# 8iPanelDec.net
KiCad netlist of a schematic drawn in EAGLE
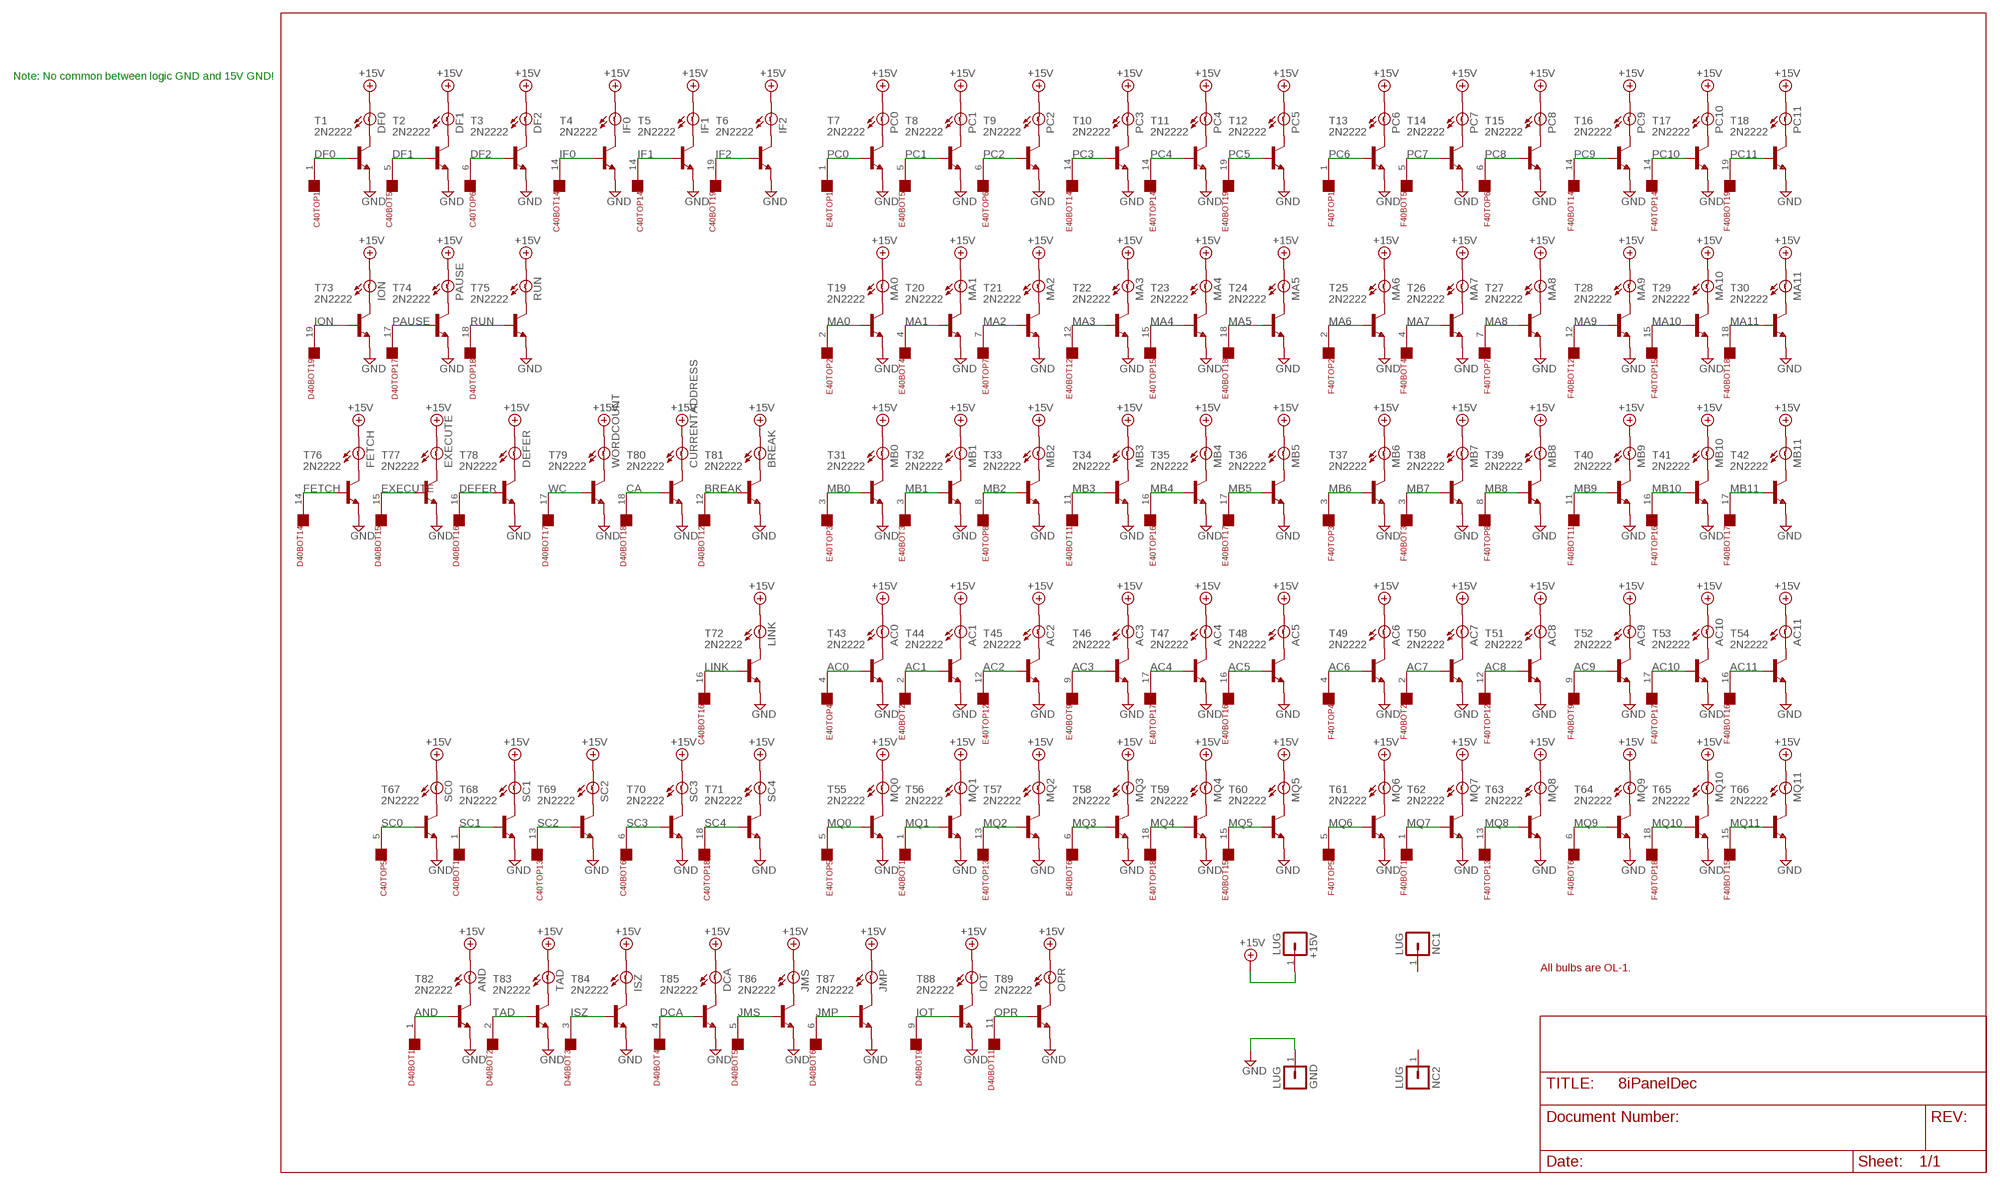
[diagram p0: schematic, sheet 1]

(export (version "E")
  (design (tool "Eeschema 10.0.6"))
  (components
    (comp (ref "+15V")
      (value "LUG")
      (footprint "eagle-import:SPADELUG")
      (libsource (lib "eagle-import") (part "LUG"))
    )
    (comp (ref "AC0")
      (value "BULB")
      (footprint "eagle-import:BULB")
      (libsource (lib "eagle-import") (part "BULB"))
    )
    (comp (ref "AC1")
      (value "BULB")
      (footprint "eagle-import:BULB")
      (libsource (lib "eagle-import") (part "BULB"))
    )
    (comp (ref "AC2")
      (value "BULB")
      (footprint "eagle-import:BULB")
      (libsource (lib "eagle-import") (part "BULB"))
    )
    (comp (ref "AC3")
      (value "BULB")
      (footprint "eagle-import:BULB")
      (libsource (lib "eagle-import") (part "BULB"))
    )
    (comp (ref "AC4")
      (value "BULB")
      (footprint "eagle-import:BULB")
      (libsource (lib "eagle-import") (part "BULB"))
    )
    (comp (ref "AC5")
      (value "BULB")
      (footprint "eagle-import:BULB")
      (libsource (lib "eagle-import") (part "BULB"))
    )
    (comp (ref "AC6")
      (value "BULB")
      (footprint "eagle-import:BULB")
      (libsource (lib "eagle-import") (part "BULB"))
    )
    (comp (ref "AC7")
      (value "BULB")
      (footprint "eagle-import:BULB")
      (libsource (lib "eagle-import") (part "BULB"))
    )
    (comp (ref "AC8")
      (value "BULB")
      (footprint "eagle-import:BULB")
      (libsource (lib "eagle-import") (part "BULB"))
    )
    (comp (ref "AC9")
      (value "BULB")
      (footprint "eagle-import:BULB")
      (libsource (lib "eagle-import") (part "BULB"))
    )
    (comp (ref "AC10")
      (value "BULB")
      (footprint "eagle-import:BULB")
      (libsource (lib "eagle-import") (part "BULB"))
    )
    (comp (ref "AC11")
      (value "BULB")
      (footprint "eagle-import:BULB")
      (libsource (lib "eagle-import") (part "BULB"))
    )
    (comp (ref "AND")
      (value "BULB")
      (footprint "eagle-import:BULB")
      (libsource (lib "eagle-import") (part "BULB"))
    )
    (comp (ref "BREAK")
      (value "BULB")
      (footprint "eagle-import:BULB")
      (libsource (lib "eagle-import") (part "BULB"))
    )
    (comp (ref "C40BOT")
      (value "FLEX19")
      (footprint "eagle-import:FLEX19")
      (libsource (lib "eagle-import") (part "FLEX19"))
    )
    (comp (ref "C40TOP")
      (value "FLEX19")
      (footprint "eagle-import:FLEX19")
      (libsource (lib "eagle-import") (part "FLEX19"))
    )
    (comp (ref "CURRENTADDRESS")
      (value "BULB")
      (footprint "eagle-import:BULB")
      (libsource (lib "eagle-import") (part "BULB"))
    )
    (comp (ref "D40BOT")
      (value "FLEX19")
      (footprint "eagle-import:FLEX19")
      (libsource (lib "eagle-import") (part "FLEX19"))
    )
    (comp (ref "D40TOP")
      (value "FLEX19")
      (footprint "eagle-import:FLEX19")
      (libsource (lib "eagle-import") (part "FLEX19"))
    )
    (comp (ref "DCA")
      (value "BULB")
      (footprint "eagle-import:BULB")
      (libsource (lib "eagle-import") (part "BULB"))
    )
    (comp (ref "DEFER")
      (value "BULB")
      (footprint "eagle-import:BULB")
      (libsource (lib "eagle-import") (part "BULB"))
    )
    (comp (ref "DF0")
      (value "BULB")
      (footprint "eagle-import:BULB")
      (libsource (lib "eagle-import") (part "BULB"))
    )
    (comp (ref "DF1")
      (value "BULB")
      (footprint "eagle-import:BULB")
      (libsource (lib "eagle-import") (part "BULB"))
    )
    (comp (ref "DF2")
      (value "BULB")
      (footprint "eagle-import:BULB")
      (libsource (lib "eagle-import") (part "BULB"))
    )
    (comp (ref "E40BOT")
      (value "FLEX19")
      (footprint "eagle-import:FLEX19")
      (libsource (lib "eagle-import") (part "FLEX19"))
    )
    (comp (ref "E40TOP")
      (value "FLEX19")
      (footprint "eagle-import:FLEX19")
      (libsource (lib "eagle-import") (part "FLEX19"))
    )
    (comp (ref "EXECUTE")
      (value "BULB")
      (footprint "eagle-import:BULB")
      (libsource (lib "eagle-import") (part "BULB"))
    )
    (comp (ref "F40BOT")
      (value "FLEX19")
      (footprint "eagle-import:FLEX19")
      (libsource (lib "eagle-import") (part "FLEX19"))
    )
    (comp (ref "F40TOP")
      (value "FLEX19")
      (footprint "eagle-import:FLEX19")
      (libsource (lib "eagle-import") (part "FLEX19"))
    )
    (comp (ref "FETCH")
      (value "BULB")
      (footprint "eagle-import:BULB")
      (libsource (lib "eagle-import") (part "BULB"))
    )
    (comp (ref "GND")
      (value "LUG")
      (footprint "eagle-import:SPADELUG")
      (libsource (lib "eagle-import") (part "LUG"))
    )
    (comp (ref "IF0")
      (value "BULB")
      (footprint "eagle-import:BULB")
      (libsource (lib "eagle-import") (part "BULB"))
    )
    (comp (ref "IF1")
      (value "BULB")
      (footprint "eagle-import:BULB")
      (libsource (lib "eagle-import") (part "BULB"))
    )
    (comp (ref "IF2")
      (value "BULB")
      (footprint "eagle-import:BULB")
      (libsource (lib "eagle-import") (part "BULB"))
    )
    (comp (ref "ION")
      (value "BULB")
      (footprint "eagle-import:BULB")
      (libsource (lib "eagle-import") (part "BULB"))
    )
    (comp (ref "IOT")
      (value "BULB")
      (footprint "eagle-import:BULB")
      (libsource (lib "eagle-import") (part "BULB"))
    )
    (comp (ref "ISZ")
      (value "BULB")
      (footprint "eagle-import:BULB")
      (libsource (lib "eagle-import") (part "BULB"))
    )
    (comp (ref "JMP")
      (value "BULB")
      (footprint "eagle-import:BULB")
      (libsource (lib "eagle-import") (part "BULB"))
    )
    (comp (ref "JMS")
      (value "BULB")
      (footprint "eagle-import:BULB")
      (libsource (lib "eagle-import") (part "BULB"))
    )
    (comp (ref "LINK")
      (value "BULB")
      (footprint "eagle-import:BULB")
      (libsource (lib "eagle-import") (part "BULB"))
    )
    (comp (ref "MA0")
      (value "BULB")
      (footprint "eagle-import:BULB")
      (libsource (lib "eagle-import") (part "BULB"))
    )
    (comp (ref "MA1")
      (value "BULB")
      (footprint "eagle-import:BULB")
      (libsource (lib "eagle-import") (part "BULB"))
    )
    (comp (ref "MA2")
      (value "BULB")
      (footprint "eagle-import:BULB")
      (libsource (lib "eagle-import") (part "BULB"))
    )
    (comp (ref "MA3")
      (value "BULB")
      (footprint "eagle-import:BULB")
      (libsource (lib "eagle-import") (part "BULB"))
    )
    (comp (ref "MA4")
      (value "BULB")
      (footprint "eagle-import:BULB")
      (libsource (lib "eagle-import") (part "BULB"))
    )
    (comp (ref "MA5")
      (value "BULB")
      (footprint "eagle-import:BULB")
      (libsource (lib "eagle-import") (part "BULB"))
    )
    (comp (ref "MA6")
      (value "BULB")
      (footprint "eagle-import:BULB")
      (libsource (lib "eagle-import") (part "BULB"))
    )
    (comp (ref "MA7")
      (value "BULB")
      (footprint "eagle-import:BULB")
      (libsource (lib "eagle-import") (part "BULB"))
    )
    (comp (ref "MA8")
      (value "BULB")
      (footprint "eagle-import:BULB")
      (libsource (lib "eagle-import") (part "BULB"))
    )
    (comp (ref "MA9")
      (value "BULB")
      (footprint "eagle-import:BULB")
      (libsource (lib "eagle-import") (part "BULB"))
    )
    (comp (ref "MA10")
      (value "BULB")
      (footprint "eagle-import:BULB")
      (libsource (lib "eagle-import") (part "BULB"))
    )
    (comp (ref "MA11")
      (value "BULB")
      (footprint "eagle-import:BULB")
      (libsource (lib "eagle-import") (part "BULB"))
    )
    (comp (ref "MB0")
      (value "BULB")
      (footprint "eagle-import:BULB")
      (libsource (lib "eagle-import") (part "BULB"))
    )
    (comp (ref "MB1")
      (value "BULB")
      (footprint "eagle-import:BULB")
      (libsource (lib "eagle-import") (part "BULB"))
    )
    (comp (ref "MB2")
      (value "BULB")
      (footprint "eagle-import:BULB")
      (libsource (lib "eagle-import") (part "BULB"))
    )
    (comp (ref "MB3")
      (value "BULB")
      (footprint "eagle-import:BULB")
      (libsource (lib "eagle-import") (part "BULB"))
    )
    (comp (ref "MB4")
      (value "BULB")
      (footprint "eagle-import:BULB")
      (libsource (lib "eagle-import") (part "BULB"))
    )
    (comp (ref "MB5")
      (value "BULB")
      (footprint "eagle-import:BULB")
      (libsource (lib "eagle-import") (part "BULB"))
    )
    (comp (ref "MB6")
      (value "BULB")
      (footprint "eagle-import:BULB")
      (libsource (lib "eagle-import") (part "BULB"))
    )
    (comp (ref "MB7")
      (value "BULB")
      (footprint "eagle-import:BULB")
      (libsource (lib "eagle-import") (part "BULB"))
    )
    (comp (ref "MB8")
      (value "BULB")
      (footprint "eagle-import:BULB")
      (libsource (lib "eagle-import") (part "BULB"))
    )
    (comp (ref "MB9")
      (value "BULB")
      (footprint "eagle-import:BULB")
      (libsource (lib "eagle-import") (part "BULB"))
    )
    (comp (ref "MB10")
      (value "BULB")
      (footprint "eagle-import:BULB")
      (libsource (lib "eagle-import") (part "BULB"))
    )
    (comp (ref "MB11")
      (value "BULB")
      (footprint "eagle-import:BULB")
      (libsource (lib "eagle-import") (part "BULB"))
    )
    (comp (ref "MQ0")
      (value "BULB")
      (footprint "eagle-import:BULB")
      (libsource (lib "eagle-import") (part "BULB"))
    )
    (comp (ref "MQ1")
      (value "BULB")
      (footprint "eagle-import:BULB")
      (libsource (lib "eagle-import") (part "BULB"))
    )
    (comp (ref "MQ2")
      (value "BULB")
      (footprint "eagle-import:BULB")
      (libsource (lib "eagle-import") (part "BULB"))
    )
    (comp (ref "MQ3")
      (value "BULB")
      (footprint "eagle-import:BULB")
      (libsource (lib "eagle-import") (part "BULB"))
    )
    (comp (ref "MQ4")
      (value "BULB")
      (footprint "eagle-import:BULB")
      (libsource (lib "eagle-import") (part "BULB"))
    )
    (comp (ref "MQ5")
      (value "BULB")
      (footprint "eagle-import:BULB")
      (libsource (lib "eagle-import") (part "BULB"))
    )
    (comp (ref "MQ6")
      (value "BULB")
      (footprint "eagle-import:BULB")
      (libsource (lib "eagle-import") (part "BULB"))
    )
    (comp (ref "MQ7")
      (value "BULB")
      (footprint "eagle-import:BULB")
      (libsource (lib "eagle-import") (part "BULB"))
    )
    (comp (ref "MQ8")
      (value "BULB")
      (footprint "eagle-import:BULB")
      (libsource (lib "eagle-import") (part "BULB"))
    )
    (comp (ref "MQ9")
      (value "BULB")
      (footprint "eagle-import:BULB")
      (libsource (lib "eagle-import") (part "BULB"))
    )
    (comp (ref "MQ10")
      (value "BULB")
      (footprint "eagle-import:BULB")
      (libsource (lib "eagle-import") (part "BULB"))
    )
    (comp (ref "MQ11")
      (value "BULB")
      (footprint "eagle-import:BULB")
      (libsource (lib "eagle-import") (part "BULB"))
    )
    (comp (ref "NC1")
      (value "LUG")
      (footprint "eagle-import:SPADELUG")
      (libsource (lib "eagle-import") (part "LUG"))
    )
    (comp (ref "NC2")
      (value "LUG")
      (footprint "eagle-import:SPADELUG")
      (libsource (lib "eagle-import") (part "LUG"))
    )
    (comp (ref "OPR")
      (value "BULB")
      (footprint "eagle-import:BULB")
      (libsource (lib "eagle-import") (part "BULB"))
    )
    (comp (ref "PAUSE")
      (value "BULB")
      (footprint "eagle-import:BULB")
      (libsource (lib "eagle-import") (part "BULB"))
    )
    (comp (ref "PC0")
      (value "BULB")
      (footprint "eagle-import:BULB")
      (libsource (lib "eagle-import") (part "BULB"))
    )
    (comp (ref "PC1")
      (value "BULB")
      (footprint "eagle-import:BULB")
      (libsource (lib "eagle-import") (part "BULB"))
    )
    (comp (ref "PC2")
      (value "BULB")
      (footprint "eagle-import:BULB")
      (libsource (lib "eagle-import") (part "BULB"))
    )
    (comp (ref "PC3")
      (value "BULB")
      (footprint "eagle-import:BULB")
      (libsource (lib "eagle-import") (part "BULB"))
    )
    (comp (ref "PC4")
      (value "BULB")
      (footprint "eagle-import:BULB")
      (libsource (lib "eagle-import") (part "BULB"))
    )
    (comp (ref "PC5")
      (value "BULB")
      (footprint "eagle-import:BULB")
      (libsource (lib "eagle-import") (part "BULB"))
    )
    (comp (ref "PC6")
      (value "BULB")
      (footprint "eagle-import:BULB")
      (libsource (lib "eagle-import") (part "BULB"))
    )
    (comp (ref "PC7")
      (value "BULB")
      (footprint "eagle-import:BULB")
      (libsource (lib "eagle-import") (part "BULB"))
    )
    (comp (ref "PC8")
      (value "BULB")
      (footprint "eagle-import:BULB")
      (libsource (lib "eagle-import") (part "BULB"))
    )
    (comp (ref "PC9")
      (value "BULB")
      (footprint "eagle-import:BULB")
      (libsource (lib "eagle-import") (part "BULB"))
    )
    (comp (ref "PC10")
      (value "BULB")
      (footprint "eagle-import:BULB")
      (libsource (lib "eagle-import") (part "BULB"))
    )
    (comp (ref "PC11")
      (value "BULB")
      (footprint "eagle-import:BULB")
      (libsource (lib "eagle-import") (part "BULB"))
    )
    (comp (ref "RUN")
      (value "BULB")
      (footprint "eagle-import:BULB")
      (libsource (lib "eagle-import") (part "BULB"))
    )
    (comp (ref "SC0")
      (value "BULB")
      (footprint "eagle-import:BULB")
      (libsource (lib "eagle-import") (part "BULB"))
    )
    (comp (ref "SC1")
      (value "BULB")
      (footprint "eagle-import:BULB")
      (libsource (lib "eagle-import") (part "BULB"))
    )
    (comp (ref "SC2")
      (value "BULB")
      (footprint "eagle-import:BULB")
      (libsource (lib "eagle-import") (part "BULB"))
    )
    (comp (ref "SC3")
      (value "BULB")
      (footprint "eagle-import:BULB")
      (libsource (lib "eagle-import") (part "BULB"))
    )
    (comp (ref "SC4")
      (value "BULB")
      (footprint "eagle-import:BULB")
      (libsource (lib "eagle-import") (part "BULB"))
    )
    (comp (ref "T1")
      (value "2N2222")
      (footprint "eagle-import:TO92")
      (libsource (lib "eagle-import") (part "-NPN-TO92"))
    )
    (comp (ref "T2")
      (value "2N2222")
      (footprint "eagle-import:TO92")
      (libsource (lib "eagle-import") (part "-NPN-TO92"))
    )
    (comp (ref "T3")
      (value "2N2222")
      (footprint "eagle-import:TO92")
      (libsource (lib "eagle-import") (part "-NPN-TO92"))
    )
    (comp (ref "T4")
      (value "2N2222")
      (footprint "eagle-import:TO92")
      (libsource (lib "eagle-import") (part "-NPN-TO92"))
    )
    (comp (ref "T5")
      (value "2N2222")
      (footprint "eagle-import:TO92")
      (libsource (lib "eagle-import") (part "-NPN-TO92"))
    )
    (comp (ref "T6")
      (value "2N2222")
      (footprint "eagle-import:TO92")
      (libsource (lib "eagle-import") (part "-NPN-TO92"))
    )
    (comp (ref "T7")
      (value "2N2222")
      (footprint "eagle-import:TO92")
      (libsource (lib "eagle-import") (part "-NPN-TO92"))
    )
    (comp (ref "T8")
      (value "2N2222")
      (footprint "eagle-import:TO92")
      (libsource (lib "eagle-import") (part "-NPN-TO92"))
    )
    (comp (ref "T9")
      (value "2N2222")
      (footprint "eagle-import:TO92")
      (libsource (lib "eagle-import") (part "-NPN-TO92"))
    )
    (comp (ref "T10")
      (value "2N2222")
      (footprint "eagle-import:TO92")
      (libsource (lib "eagle-import") (part "-NPN-TO92"))
    )
    (comp (ref "T11")
      (value "2N2222")
      (footprint "eagle-import:TO92")
      (libsource (lib "eagle-import") (part "-NPN-TO92"))
    )
    (comp (ref "T12")
      (value "2N2222")
      (footprint "eagle-import:TO92")
      (libsource (lib "eagle-import") (part "-NPN-TO92"))
    )
    (comp (ref "T13")
      (value "2N2222")
      (footprint "eagle-import:TO92")
      (libsource (lib "eagle-import") (part "-NPN-TO92"))
    )
    (comp (ref "T14")
      (value "2N2222")
      (footprint "eagle-import:TO92")
      (libsource (lib "eagle-import") (part "-NPN-TO92"))
    )
    (comp (ref "T15")
      (value "2N2222")
      (footprint "eagle-import:TO92")
      (libsource (lib "eagle-import") (part "-NPN-TO92"))
    )
    (comp (ref "T16")
      (value "2N2222")
      (footprint "eagle-import:TO92")
      (libsource (lib "eagle-import") (part "-NPN-TO92"))
    )
    (comp (ref "T17")
      (value "2N2222")
      (footprint "eagle-import:TO92")
      (libsource (lib "eagle-import") (part "-NPN-TO92"))
    )
    (comp (ref "T18")
      (value "2N2222")
      (footprint "eagle-import:TO92")
      (libsource (lib "eagle-import") (part "-NPN-TO92"))
    )
    (comp (ref "T19")
      (value "2N2222")
      (footprint "eagle-import:TO92")
      (libsource (lib "eagle-import") (part "-NPN-TO92"))
    )
    (comp (ref "T20")
      (value "2N2222")
      (footprint "eagle-import:TO92")
      (libsource (lib "eagle-import") (part "-NPN-TO92"))
    )
    (comp (ref "T21")
      (value "2N2222")
      (footprint "eagle-import:TO92")
      (libsource (lib "eagle-import") (part "-NPN-TO92"))
    )
    (comp (ref "T22")
      (value "2N2222")
      (footprint "eagle-import:TO92")
      (libsource (lib "eagle-import") (part "-NPN-TO92"))
    )
    (comp (ref "T23")
      (value "2N2222")
      (footprint "eagle-import:TO92")
      (libsource (lib "eagle-import") (part "-NPN-TO92"))
    )
    (comp (ref "T24")
      (value "2N2222")
      (footprint "eagle-import:TO92")
      (libsource (lib "eagle-import") (part "-NPN-TO92"))
    )
    (comp (ref "T25")
      (value "2N2222")
      (footprint "eagle-import:TO92")
      (libsource (lib "eagle-import") (part "-NPN-TO92"))
    )
    (comp (ref "T26")
      (value "2N2222")
      (footprint "eagle-import:TO92")
      (libsource (lib "eagle-import") (part "-NPN-TO92"))
    )
    (comp (ref "T27")
      (value "2N2222")
      (footprint "eagle-import:TO92")
      (libsource (lib "eagle-import") (part "-NPN-TO92"))
    )
    (comp (ref "T28")
      (value "2N2222")
      (footprint "eagle-import:TO92")
      (libsource (lib "eagle-import") (part "-NPN-TO92"))
    )
    (comp (ref "T29")
      (value "2N2222")
      (footprint "eagle-import:TO92")
      (libsource (lib "eagle-import") (part "-NPN-TO92"))
    )
    (comp (ref "T30")
      (value "2N2222")
      (footprint "eagle-import:TO92")
      (libsource (lib "eagle-import") (part "-NPN-TO92"))
    )
    (comp (ref "T31")
      (value "2N2222")
      (footprint "eagle-import:TO92")
      (libsource (lib "eagle-import") (part "-NPN-TO92"))
    )
    (comp (ref "T32")
      (value "2N2222")
      (footprint "eagle-import:TO92")
      (libsource (lib "eagle-import") (part "-NPN-TO92"))
    )
    (comp (ref "T33")
      (value "2N2222")
      (footprint "eagle-import:TO92")
      (libsource (lib "eagle-import") (part "-NPN-TO92"))
    )
    (comp (ref "T34")
      (value "2N2222")
      (footprint "eagle-import:TO92")
      (libsource (lib "eagle-import") (part "-NPN-TO92"))
    )
    (comp (ref "T35")
      (value "2N2222")
      (footprint "eagle-import:TO92")
      (libsource (lib "eagle-import") (part "-NPN-TO92"))
    )
    (comp (ref "T36")
      (value "2N2222")
      (footprint "eagle-import:TO92")
      (libsource (lib "eagle-import") (part "-NPN-TO92"))
    )
    (comp (ref "T37")
      (value "2N2222")
      (footprint "eagle-import:TO92")
      (libsource (lib "eagle-import") (part "-NPN-TO92"))
    )
    (comp (ref "T38")
      (value "2N2222")
      (footprint "eagle-import:TO92")
      (libsource (lib "eagle-import") (part "-NPN-TO92"))
    )
    (comp (ref "T39")
      (value "2N2222")
      (footprint "eagle-import:TO92")
      (libsource (lib "eagle-import") (part "-NPN-TO92"))
    )
    (comp (ref "T40")
      (value "2N2222")
      (footprint "eagle-import:TO92")
      (libsource (lib "eagle-import") (part "-NPN-TO92"))
    )
    (comp (ref "T41")
      (value "2N2222")
      (footprint "eagle-import:TO92")
      (libsource (lib "eagle-import") (part "-NPN-TO92"))
    )
    (comp (ref "T42")
      (value "2N2222")
      (footprint "eagle-import:TO92")
      (libsource (lib "eagle-import") (part "-NPN-TO92"))
    )
    (comp (ref "T43")
      (value "2N2222")
      (footprint "eagle-import:TO92")
      (libsource (lib "eagle-import") (part "-NPN-TO92"))
    )
    (comp (ref "T44")
      (value "2N2222")
      (footprint "eagle-import:TO92")
      (libsource (lib "eagle-import") (part "-NPN-TO92"))
    )
    (comp (ref "T45")
      (value "2N2222")
      (footprint "eagle-import:TO92")
      (libsource (lib "eagle-import") (part "-NPN-TO92"))
    )
    (comp (ref "T46")
      (value "2N2222")
      (footprint "eagle-import:TO92")
      (libsource (lib "eagle-import") (part "-NPN-TO92"))
    )
    (comp (ref "T47")
      (value "2N2222")
      (footprint "eagle-import:TO92")
      (libsource (lib "eagle-import") (part "-NPN-TO92"))
    )
    (comp (ref "T48")
      (value "2N2222")
      (footprint "eagle-import:TO92")
      (libsource (lib "eagle-import") (part "-NPN-TO92"))
    )
    (comp (ref "T49")
      (value "2N2222")
      (footprint "eagle-import:TO92")
      (libsource (lib "eagle-import") (part "-NPN-TO92"))
    )
    (comp (ref "T50")
      (value "2N2222")
      (footprint "eagle-import:TO92")
      (libsource (lib "eagle-import") (part "-NPN-TO92"))
    )
    (comp (ref "T51")
      (value "2N2222")
      (footprint "eagle-import:TO92")
      (libsource (lib "eagle-import") (part "-NPN-TO92"))
    )
    (comp (ref "T52")
      (value "2N2222")
      (footprint "eagle-import:TO92")
      (libsource (lib "eagle-import") (part "-NPN-TO92"))
    )
    (comp (ref "T53")
      (value "2N2222")
      (footprint "eagle-import:TO92")
      (libsource (lib "eagle-import") (part "-NPN-TO92"))
    )
    (comp (ref "T54")
      (value "2N2222")
      (footprint "eagle-import:TO92")
      (libsource (lib "eagle-import") (part "-NPN-TO92"))
    )
    (comp (ref "T55")
      (value "2N2222")
      (footprint "eagle-import:TO92")
      (libsource (lib "eagle-import") (part "-NPN-TO92"))
    )
    (comp (ref "T56")
      (value "2N2222")
      (footprint "eagle-import:TO92")
      (libsource (lib "eagle-import") (part "-NPN-TO92"))
    )
    (comp (ref "T57")
      (value "2N2222")
      (footprint "eagle-import:TO92")
      (libsource (lib "eagle-import") (part "-NPN-TO92"))
    )
    (comp (ref "T58")
      (value "2N2222")
      (footprint "eagle-import:TO92")
      (libsource (lib "eagle-import") (part "-NPN-TO92"))
    )
    (comp (ref "T59")
      (value "2N2222")
      (footprint "eagle-import:TO92")
      (libsource (lib "eagle-import") (part "-NPN-TO92"))
    )
    (comp (ref "T60")
      (value "2N2222")
      (footprint "eagle-import:TO92")
      (libsource (lib "eagle-import") (part "-NPN-TO92"))
    )
    (comp (ref "T61")
      (value "2N2222")
      (footprint "eagle-import:TO92")
      (libsource (lib "eagle-import") (part "-NPN-TO92"))
    )
    (comp (ref "T62")
      (value "2N2222")
      (footprint "eagle-import:TO92")
      (libsource (lib "eagle-import") (part "-NPN-TO92"))
    )
    (comp (ref "T63")
      (value "2N2222")
      (footprint "eagle-import:TO92")
      (libsource (lib "eagle-import") (part "-NPN-TO92"))
    )
    (comp (ref "T64")
      (value "2N2222")
      (footprint "eagle-import:TO92")
      (libsource (lib "eagle-import") (part "-NPN-TO92"))
    )
    (comp (ref "T65")
      (value "2N2222")
      (footprint "eagle-import:TO92")
      (libsource (lib "eagle-import") (part "-NPN-TO92"))
    )
    (comp (ref "T66")
      (value "2N2222")
      (footprint "eagle-import:TO92")
      (libsource (lib "eagle-import") (part "-NPN-TO92"))
    )
    (comp (ref "T67")
      (value "2N2222")
      (footprint "eagle-import:TO92")
      (libsource (lib "eagle-import") (part "-NPN-TO92"))
    )
    (comp (ref "T68")
      (value "2N2222")
      (footprint "eagle-import:TO92")
      (libsource (lib "eagle-import") (part "-NPN-TO92"))
    )
    (comp (ref "T69")
      (value "2N2222")
      (footprint "eagle-import:TO92")
      (libsource (lib "eagle-import") (part "-NPN-TO92"))
    )
    (comp (ref "T70")
      (value "2N2222")
      (footprint "eagle-import:TO92")
      (libsource (lib "eagle-import") (part "-NPN-TO92"))
    )
    (comp (ref "T71")
      (value "2N2222")
      (footprint "eagle-import:TO92")
      (libsource (lib "eagle-import") (part "-NPN-TO92"))
    )
    (comp (ref "T72")
      (value "2N2222")
      (footprint "eagle-import:TO92")
      (libsource (lib "eagle-import") (part "-NPN-TO92"))
    )
    (comp (ref "T73")
      (value "2N2222")
      (footprint "eagle-import:TO92")
      (libsource (lib "eagle-import") (part "-NPN-TO92"))
    )
    (comp (ref "T74")
      (value "2N2222")
      (footprint "eagle-import:TO92")
      (libsource (lib "eagle-import") (part "-NPN-TO92"))
    )
    (comp (ref "T75")
      (value "2N2222")
      (footprint "eagle-import:TO92")
      (libsource (lib "eagle-import") (part "-NPN-TO92"))
    )
    (comp (ref "T76")
      (value "2N2222")
      (footprint "eagle-import:TO92")
      (libsource (lib "eagle-import") (part "-NPN-TO92"))
    )
    (comp (ref "T77")
      (value "2N2222")
      (footprint "eagle-import:TO92")
      (libsource (lib "eagle-import") (part "-NPN-TO92"))
    )
    (comp (ref "T78")
      (value "2N2222")
      (footprint "eagle-import:TO92")
      (libsource (lib "eagle-import") (part "-NPN-TO92"))
    )
    (comp (ref "T79")
      (value "2N2222")
      (footprint "eagle-import:TO92")
      (libsource (lib "eagle-import") (part "-NPN-TO92"))
    )
    (comp (ref "T80")
      (value "2N2222")
      (footprint "eagle-import:TO92")
      (libsource (lib "eagle-import") (part "-NPN-TO92"))
    )
    (comp (ref "T81")
      (value "2N2222")
      (footprint "eagle-import:TO92")
      (libsource (lib "eagle-import") (part "-NPN-TO92"))
    )
    (comp (ref "T82")
      (value "2N2222")
      (footprint "eagle-import:TO92")
      (libsource (lib "eagle-import") (part "-NPN-TO92"))
    )
    (comp (ref "T83")
      (value "2N2222")
      (footprint "eagle-import:TO92")
      (libsource (lib "eagle-import") (part "-NPN-TO92"))
    )
    (comp (ref "T84")
      (value "2N2222")
      (footprint "eagle-import:TO92")
      (libsource (lib "eagle-import") (part "-NPN-TO92"))
    )
    (comp (ref "T85")
      (value "2N2222")
      (footprint "eagle-import:TO92")
      (libsource (lib "eagle-import") (part "-NPN-TO92"))
    )
    (comp (ref "T86")
      (value "2N2222")
      (footprint "eagle-import:TO92")
      (libsource (lib "eagle-import") (part "-NPN-TO92"))
    )
    (comp (ref "T87")
      (value "2N2222")
      (footprint "eagle-import:TO92")
      (libsource (lib "eagle-import") (part "-NPN-TO92"))
    )
    (comp (ref "T88")
      (value "2N2222")
      (footprint "eagle-import:TO92")
      (libsource (lib "eagle-import") (part "-NPN-TO92"))
    )
    (comp (ref "T89")
      (value "2N2222")
      (footprint "eagle-import:TO92")
      (libsource (lib "eagle-import") (part "-NPN-TO92"))
    )
    (comp (ref "TAD")
      (value "BULB")
      (footprint "eagle-import:BULB")
      (libsource (lib "eagle-import") (part "BULB"))
    )
    (comp (ref "WORDCOUNT")
      (value "BULB")
      (footprint "eagle-import:BULB")
      (libsource (lib "eagle-import") (part "BULB"))
    )
  )
  (nets
    (net (code "1") (name "+15V") (class "Default")
      (node (ref "+15V") (pin "1") (pinfunction "1_1") (pintype "passive"))
      (node (ref "AC0") (pin "A") (pinfunction "A_A") (pintype "passive"))
      (node (ref "AC1") (pin "A") (pinfunction "A_A") (pintype "passive"))
      (node (ref "AC10") (pin "A") (pinfunction "A_A") (pintype "passive"))
      (node (ref "AC11") (pin "A") (pinfunction "A_A") (pintype "passive"))
      (node (ref "AC2") (pin "A") (pinfunction "A_A") (pintype "passive"))
      (node (ref "AC3") (pin "A") (pinfunction "A_A") (pintype "passive"))
      (node (ref "AC4") (pin "A") (pinfunction "A_A") (pintype "passive"))
      (node (ref "AC5") (pin "A") (pinfunction "A_A") (pintype "passive"))
      (node (ref "AC6") (pin "A") (pinfunction "A_A") (pintype "passive"))
      (node (ref "AC7") (pin "A") (pinfunction "A_A") (pintype "passive"))
      (node (ref "AC8") (pin "A") (pinfunction "A_A") (pintype "passive"))
      (node (ref "AC9") (pin "A") (pinfunction "A_A") (pintype "passive"))
      (node (ref "AND") (pin "A") (pinfunction "A_A") (pintype "passive"))
      (node (ref "BREAK") (pin "A") (pinfunction "A_A") (pintype "passive"))
      (node (ref "CURRENTADDRESS") (pin "A") (pinfunction "A_A") (pintype "passive"))
      (node (ref "DCA") (pin "A") (pinfunction "A_A") (pintype "passive"))
      (node (ref "DEFER") (pin "A") (pinfunction "A_A") (pintype "passive"))
      (node (ref "DF0") (pin "A") (pinfunction "A_A") (pintype "passive"))
      (node (ref "DF1") (pin "A") (pinfunction "A_A") (pintype "passive"))
      (node (ref "DF2") (pin "A") (pinfunction "A_A") (pintype "passive"))
      (node (ref "EXECUTE") (pin "A") (pinfunction "A_A") (pintype "passive"))
      (node (ref "FETCH") (pin "A") (pinfunction "A_A") (pintype "passive"))
      (node (ref "IF0") (pin "A") (pinfunction "A_A") (pintype "passive"))
      (node (ref "IF1") (pin "A") (pinfunction "A_A") (pintype "passive"))
      (node (ref "IF2") (pin "A") (pinfunction "A_A") (pintype "passive"))
      (node (ref "ION") (pin "A") (pinfunction "A_A") (pintype "passive"))
      (node (ref "IOT") (pin "A") (pinfunction "A_A") (pintype "passive"))
      (node (ref "ISZ") (pin "A") (pinfunction "A_A") (pintype "passive"))
      (node (ref "JMP") (pin "A") (pinfunction "A_A") (pintype "passive"))
      (node (ref "JMS") (pin "A") (pinfunction "A_A") (pintype "passive"))
      (node (ref "LINK") (pin "A") (pinfunction "A_A") (pintype "passive"))
      (node (ref "MA0") (pin "A") (pinfunction "A_A") (pintype "passive"))
      (node (ref "MA1") (pin "A") (pinfunction "A_A") (pintype "passive"))
      (node (ref "MA10") (pin "A") (pinfunction "A_A") (pintype "passive"))
      (node (ref "MA11") (pin "A") (pinfunction "A_A") (pintype "passive"))
      (node (ref "MA2") (pin "A") (pinfunction "A_A") (pintype "passive"))
      (node (ref "MA3") (pin "A") (pinfunction "A_A") (pintype "passive"))
      (node (ref "MA4") (pin "A") (pinfunction "A_A") (pintype "passive"))
      (node (ref "MA5") (pin "A") (pinfunction "A_A") (pintype "passive"))
      (node (ref "MA6") (pin "A") (pinfunction "A_A") (pintype "passive"))
      (node (ref "MA7") (pin "A") (pinfunction "A_A") (pintype "passive"))
      (node (ref "MA8") (pin "A") (pinfunction "A_A") (pintype "passive"))
      (node (ref "MA9") (pin "A") (pinfunction "A_A") (pintype "passive"))
      (node (ref "MB0") (pin "A") (pinfunction "A_A") (pintype "passive"))
      (node (ref "MB1") (pin "A") (pinfunction "A_A") (pintype "passive"))
      (node (ref "MB10") (pin "A") (pinfunction "A_A") (pintype "passive"))
      (node (ref "MB11") (pin "A") (pinfunction "A_A") (pintype "passive"))
      (node (ref "MB2") (pin "A") (pinfunction "A_A") (pintype "passive"))
      (node (ref "MB3") (pin "A") (pinfunction "A_A") (pintype "passive"))
      (node (ref "MB4") (pin "A") (pinfunction "A_A") (pintype "passive"))
      (node (ref "MB5") (pin "A") (pinfunction "A_A") (pintype "passive"))
      (node (ref "MB6") (pin "A") (pinfunction "A_A") (pintype "passive"))
      (node (ref "MB7") (pin "A") (pinfunction "A_A") (pintype "passive"))
      (node (ref "MB8") (pin "A") (pinfunction "A_A") (pintype "passive"))
      (node (ref "MB9") (pin "A") (pinfunction "A_A") (pintype "passive"))
      (node (ref "MQ0") (pin "A") (pinfunction "A_A") (pintype "passive"))
      (node (ref "MQ1") (pin "A") (pinfunction "A_A") (pintype "passive"))
      (node (ref "MQ10") (pin "A") (pinfunction "A_A") (pintype "passive"))
      (node (ref "MQ11") (pin "A") (pinfunction "A_A") (pintype "passive"))
      (node (ref "MQ2") (pin "A") (pinfunction "A_A") (pintype "passive"))
      (node (ref "MQ3") (pin "A") (pinfunction "A_A") (pintype "passive"))
      (node (ref "MQ4") (pin "A") (pinfunction "A_A") (pintype "passive"))
      (node (ref "MQ5") (pin "A") (pinfunction "A_A") (pintype "passive"))
      (node (ref "MQ6") (pin "A") (pinfunction "A_A") (pintype "passive"))
      (node (ref "MQ7") (pin "A") (pinfunction "A_A") (pintype "passive"))
      (node (ref "MQ8") (pin "A") (pinfunction "A_A") (pintype "passive"))
      (node (ref "MQ9") (pin "A") (pinfunction "A_A") (pintype "passive"))
      (node (ref "OPR") (pin "A") (pinfunction "A_A") (pintype "passive"))
      (node (ref "PAUSE") (pin "A") (pinfunction "A_A") (pintype "passive"))
      (node (ref "PC0") (pin "A") (pinfunction "A_A") (pintype "passive"))
      (node (ref "PC1") (pin "A") (pinfunction "A_A") (pintype "passive"))
      (node (ref "PC10") (pin "A") (pinfunction "A_A") (pintype "passive"))
      (node (ref "PC11") (pin "A") (pinfunction "A_A") (pintype "passive"))
      (node (ref "PC2") (pin "A") (pinfunction "A_A") (pintype "passive"))
      (node (ref "PC3") (pin "A") (pinfunction "A_A") (pintype "passive"))
      (node (ref "PC4") (pin "A") (pinfunction "A_A") (pintype "passive"))
      (node (ref "PC5") (pin "A") (pinfunction "A_A") (pintype "passive"))
      (node (ref "PC6") (pin "A") (pinfunction "A_A") (pintype "passive"))
      (node (ref "PC7") (pin "A") (pinfunction "A_A") (pintype "passive"))
      (node (ref "PC8") (pin "A") (pinfunction "A_A") (pintype "passive"))
      (node (ref "PC9") (pin "A") (pinfunction "A_A") (pintype "passive"))
      (node (ref "RUN") (pin "A") (pinfunction "A_A") (pintype "passive"))
      (node (ref "SC0") (pin "A") (pinfunction "A_A") (pintype "passive"))
      (node (ref "SC1") (pin "A") (pinfunction "A_A") (pintype "passive"))
      (node (ref "SC2") (pin "A") (pinfunction "A_A") (pintype "passive"))
      (node (ref "SC3") (pin "A") (pinfunction "A_A") (pintype "passive"))
      (node (ref "SC4") (pin "A") (pinfunction "A_A") (pintype "passive"))
      (node (ref "TAD") (pin "A") (pinfunction "A_A") (pintype "passive"))
      (node (ref "WORDCOUNT") (pin "A") (pinfunction "A_A") (pintype "passive"))
    )
    (net (code "2") (name "/AC0") (class "Default")
      (node (ref "E40TOP") (pin "4") (pinfunction "1_4") (pintype "passive"))
      (node (ref "T43") (pin "2") (pinfunction "B_2") (pintype "passive"))
    )
    (net (code "3") (name "/AC1") (class "Default")
      (node (ref "E40BOT") (pin "2") (pinfunction "1_2") (pintype "passive"))
      (node (ref "T44") (pin "2") (pinfunction "B_2") (pintype "passive"))
    )
    (net (code "4") (name "/AC2") (class "Default")
      (node (ref "E40TOP") (pin "12") (pinfunction "1_12") (pintype "passive"))
      (node (ref "T45") (pin "2") (pinfunction "B_2") (pintype "passive"))
    )
    (net (code "5") (name "/AC3") (class "Default")
      (node (ref "E40BOT") (pin "9") (pinfunction "1_9") (pintype "passive"))
      (node (ref "T46") (pin "2") (pinfunction "B_2") (pintype "passive"))
    )
    (net (code "6") (name "/AC4") (class "Default")
      (node (ref "E40TOP") (pin "17") (pinfunction "1_17") (pintype "passive"))
      (node (ref "T47") (pin "2") (pinfunction "B_2") (pintype "passive"))
    )
    (net (code "7") (name "/AC5") (class "Default")
      (node (ref "E40BOT") (pin "16") (pinfunction "1_16") (pintype "passive"))
      (node (ref "T48") (pin "2") (pinfunction "B_2") (pintype "passive"))
    )
    (net (code "8") (name "/AC6") (class "Default")
      (node (ref "F40TOP") (pin "4") (pinfunction "1_4") (pintype "passive"))
      (node (ref "T49") (pin "2") (pinfunction "B_2") (pintype "passive"))
    )
    (net (code "9") (name "/AC7") (class "Default")
      (node (ref "F40BOT") (pin "2") (pinfunction "1_2") (pintype "passive"))
      (node (ref "T50") (pin "2") (pinfunction "B_2") (pintype "passive"))
    )
    (net (code "10") (name "/AC8") (class "Default")
      (node (ref "F40TOP") (pin "12") (pinfunction "1_12") (pintype "passive"))
      (node (ref "T51") (pin "2") (pinfunction "B_2") (pintype "passive"))
    )
    (net (code "11") (name "/AC9") (class "Default")
      (node (ref "F40BOT") (pin "9") (pinfunction "1_9") (pintype "passive"))
      (node (ref "T52") (pin "2") (pinfunction "B_2") (pintype "passive"))
    )
    (net (code "12") (name "/AC10") (class "Default")
      (node (ref "F40TOP") (pin "17") (pinfunction "1_17") (pintype "passive"))
      (node (ref "T53") (pin "2") (pinfunction "B_2") (pintype "passive"))
    )
    (net (code "13") (name "/AC11") (class "Default")
      (node (ref "F40BOT") (pin "16") (pinfunction "1_16") (pintype "passive"))
      (node (ref "T54") (pin "2") (pinfunction "B_2") (pintype "passive"))
    )
    (net (code "14") (name "/AND") (class "Default")
      (node (ref "D40BOT") (pin "1") (pinfunction "1_1") (pintype "passive"))
      (node (ref "T82") (pin "2") (pinfunction "B_2") (pintype "passive"))
    )
    (net (code "15") (name "/BREAK") (class "Default")
      (node (ref "D40BOT") (pin "12") (pinfunction "1_12") (pintype "passive"))
      (node (ref "T81") (pin "2") (pinfunction "B_2") (pintype "passive"))
    )
    (net (code "16") (name "/CA") (class "Default")
      (node (ref "D40BOT") (pin "18") (pinfunction "1_18") (pintype "passive"))
      (node (ref "T80") (pin "2") (pinfunction "B_2") (pintype "passive"))
    )
    (net (code "17") (name "/DCA") (class "Default")
      (node (ref "D40BOT") (pin "4") (pinfunction "1_4") (pintype "passive"))
      (node (ref "T85") (pin "2") (pinfunction "B_2") (pintype "passive"))
    )
    (net (code "18") (name "/DEFER") (class "Default")
      (node (ref "D40BOT") (pin "16") (pinfunction "1_16") (pintype "passive"))
      (node (ref "T78") (pin "2") (pinfunction "B_2") (pintype "passive"))
    )
    (net (code "19") (name "/DF0") (class "Default")
      (node (ref "C40TOP") (pin "1") (pinfunction "1_1") (pintype "passive"))
      (node (ref "T1") (pin "2") (pinfunction "B_2") (pintype "passive"))
    )
    (net (code "20") (name "/DF1") (class "Default")
      (node (ref "C40BOT") (pin "5") (pinfunction "1_5") (pintype "passive"))
      (node (ref "T2") (pin "2") (pinfunction "B_2") (pintype "passive"))
    )
    (net (code "21") (name "/DF2") (class "Default")
      (node (ref "C40TOP") (pin "6") (pinfunction "1_6") (pintype "passive"))
      (node (ref "T3") (pin "2") (pinfunction "B_2") (pintype "passive"))
    )
    (net (code "22") (name "/EXECUTE") (class "Default")
      (node (ref "D40BOT") (pin "15") (pinfunction "1_15") (pintype "passive"))
      (node (ref "T77") (pin "2") (pinfunction "B_2") (pintype "passive"))
    )
    (net (code "23") (name "/FETCH") (class "Default")
      (node (ref "D40BOT") (pin "14") (pinfunction "1_14") (pintype "passive"))
      (node (ref "T76") (pin "2") (pinfunction "B_2") (pintype "passive"))
    )
    (net (code "24") (name "/IF0") (class "Default")
      (node (ref "C40BOT") (pin "14") (pinfunction "1_14") (pintype "passive"))
      (node (ref "T4") (pin "2") (pinfunction "B_2") (pintype "passive"))
    )
    (net (code "25") (name "/IF1") (class "Default")
      (node (ref "C40TOP") (pin "14") (pinfunction "1_14") (pintype "passive"))
      (node (ref "T5") (pin "2") (pinfunction "B_2") (pintype "passive"))
    )
    (net (code "26") (name "/IF2") (class "Default")
      (node (ref "C40BOT") (pin "19") (pinfunction "1_19") (pintype "passive"))
      (node (ref "T6") (pin "2") (pinfunction "B_2") (pintype "passive"))
    )
    (net (code "27") (name "/ION") (class "Default")
      (node (ref "D40BOT") (pin "19") (pinfunction "1_19") (pintype "passive"))
      (node (ref "T73") (pin "2") (pinfunction "B_2") (pintype "passive"))
    )
    (net (code "28") (name "/IOT") (class "Default")
      (node (ref "D40BOT") (pin "9") (pinfunction "1_9") (pintype "passive"))
      (node (ref "T88") (pin "2") (pinfunction "B_2") (pintype "passive"))
    )
    (net (code "29") (name "/ISZ") (class "Default")
      (node (ref "D40BOT") (pin "3") (pinfunction "1_3") (pintype "passive"))
      (node (ref "T84") (pin "2") (pinfunction "B_2") (pintype "passive"))
    )
    (net (code "30") (name "/JMP") (class "Default")
      (node (ref "D40BOT") (pin "6") (pinfunction "1_6") (pintype "passive"))
      (node (ref "T87") (pin "2") (pinfunction "B_2") (pintype "passive"))
    )
    (net (code "31") (name "/JMS") (class "Default")
      (node (ref "D40BOT") (pin "5") (pinfunction "1_5") (pintype "passive"))
      (node (ref "T86") (pin "2") (pinfunction "B_2") (pintype "passive"))
    )
    (net (code "32") (name "/LINK") (class "Default")
      (node (ref "C40BOT") (pin "16") (pinfunction "1_16") (pintype "passive"))
      (node (ref "T72") (pin "2") (pinfunction "B_2") (pintype "passive"))
    )
    (net (code "33") (name "/MA0") (class "Default")
      (node (ref "E40TOP") (pin "2") (pinfunction "1_2") (pintype "passive"))
      (node (ref "T19") (pin "2") (pinfunction "B_2") (pintype "passive"))
    )
    (net (code "34") (name "/MA1") (class "Default")
      (node (ref "E40BOT") (pin "4") (pinfunction "1_4") (pintype "passive"))
      (node (ref "T20") (pin "2") (pinfunction "B_2") (pintype "passive"))
    )
    (net (code "35") (name "/MA2") (class "Default")
      (node (ref "E40TOP") (pin "7") (pinfunction "1_7") (pintype "passive"))
      (node (ref "T21") (pin "2") (pinfunction "B_2") (pintype "passive"))
    )
    (net (code "36") (name "/MA3") (class "Default")
      (node (ref "E40BOT") (pin "12") (pinfunction "1_12") (pintype "passive"))
      (node (ref "T22") (pin "2") (pinfunction "B_2") (pintype "passive"))
    )
    (net (code "37") (name "/MA4") (class "Default")
      (node (ref "E40TOP") (pin "15") (pinfunction "1_15") (pintype "passive"))
      (node (ref "T23") (pin "2") (pinfunction "B_2") (pintype "passive"))
    )
    (net (code "38") (name "/MA5") (class "Default")
      (node (ref "E40BOT") (pin "18") (pinfunction "1_18") (pintype "passive"))
      (node (ref "T24") (pin "2") (pinfunction "B_2") (pintype "passive"))
    )
    (net (code "39") (name "/MA6") (class "Default")
      (node (ref "F40TOP") (pin "2") (pinfunction "1_2") (pintype "passive"))
      (node (ref "T25") (pin "2") (pinfunction "B_2") (pintype "passive"))
    )
    (net (code "40") (name "/MA7") (class "Default")
      (node (ref "F40BOT") (pin "4") (pinfunction "1_4") (pintype "passive"))
      (node (ref "T26") (pin "2") (pinfunction "B_2") (pintype "passive"))
    )
    (net (code "41") (name "/MA8") (class "Default")
      (node (ref "F40TOP") (pin "7") (pinfunction "1_7") (pintype "passive"))
      (node (ref "T27") (pin "2") (pinfunction "B_2") (pintype "passive"))
    )
    (net (code "42") (name "/MA9") (class "Default")
      (node (ref "F40BOT") (pin "12") (pinfunction "1_12") (pintype "passive"))
      (node (ref "T28") (pin "2") (pinfunction "B_2") (pintype "passive"))
    )
    (net (code "43") (name "/MA10") (class "Default")
      (node (ref "F40TOP") (pin "15") (pinfunction "1_15") (pintype "passive"))
      (node (ref "T29") (pin "2") (pinfunction "B_2") (pintype "passive"))
    )
    (net (code "44") (name "/MA11") (class "Default")
      (node (ref "F40BOT") (pin "18") (pinfunction "1_18") (pintype "passive"))
      (node (ref "T30") (pin "2") (pinfunction "B_2") (pintype "passive"))
    )
    (net (code "45") (name "/MB0") (class "Default")
      (node (ref "E40TOP") (pin "3") (pinfunction "1_3") (pintype "passive"))
      (node (ref "T31") (pin "2") (pinfunction "B_2") (pintype "passive"))
    )
    (net (code "46") (name "/MB1") (class "Default")
      (node (ref "E40BOT") (pin "3") (pinfunction "1_3") (pintype "passive"))
      (node (ref "T32") (pin "2") (pinfunction "B_2") (pintype "passive"))
    )
    (net (code "47") (name "/MB2") (class "Default")
      (node (ref "E40TOP") (pin "8") (pinfunction "1_8") (pintype "passive"))
      (node (ref "T33") (pin "2") (pinfunction "B_2") (pintype "passive"))
    )
    (net (code "48") (name "/MB3") (class "Default")
      (node (ref "E40BOT") (pin "11") (pinfunction "1_11") (pintype "passive"))
      (node (ref "T34") (pin "2") (pinfunction "B_2") (pintype "passive"))
    )
    (net (code "49") (name "/MB4") (class "Default")
      (node (ref "E40TOP") (pin "16") (pinfunction "1_16") (pintype "passive"))
      (node (ref "T35") (pin "2") (pinfunction "B_2") (pintype "passive"))
    )
    (net (code "50") (name "/MB5") (class "Default")
      (node (ref "E40BOT") (pin "17") (pinfunction "1_17") (pintype "passive"))
      (node (ref "T36") (pin "2") (pinfunction "B_2") (pintype "passive"))
    )
    (net (code "51") (name "/MB6") (class "Default")
      (node (ref "F40TOP") (pin "3") (pinfunction "1_3") (pintype "passive"))
      (node (ref "T37") (pin "2") (pinfunction "B_2") (pintype "passive"))
    )
    (net (code "52") (name "/MB7") (class "Default")
      (node (ref "F40BOT") (pin "3") (pinfunction "1_3") (pintype "passive"))
      (node (ref "T38") (pin "2") (pinfunction "B_2") (pintype "passive"))
    )
    (net (code "53") (name "/MB8") (class "Default")
      (node (ref "F40TOP") (pin "8") (pinfunction "1_8") (pintype "passive"))
      (node (ref "T39") (pin "2") (pinfunction "B_2") (pintype "passive"))
    )
    (net (code "54") (name "/MB9") (class "Default")
      (node (ref "F40BOT") (pin "11") (pinfunction "1_11") (pintype "passive"))
      (node (ref "T40") (pin "2") (pinfunction "B_2") (pintype "passive"))
    )
    (net (code "55") (name "/MB10") (class "Default")
      (node (ref "F40TOP") (pin "16") (pinfunction "1_16") (pintype "passive"))
      (node (ref "T41") (pin "2") (pinfunction "B_2") (pintype "passive"))
    )
    (net (code "56") (name "/MB11") (class "Default")
      (node (ref "F40BOT") (pin "17") (pinfunction "1_17") (pintype "passive"))
      (node (ref "T42") (pin "2") (pinfunction "B_2") (pintype "passive"))
    )
    (net (code "57") (name "/MQ0") (class "Default")
      (node (ref "E40TOP") (pin "5") (pinfunction "1_5") (pintype "passive"))
      (node (ref "T55") (pin "2") (pinfunction "B_2") (pintype "passive"))
    )
    (net (code "58") (name "/MQ1") (class "Default")
      (node (ref "E40BOT") (pin "1") (pinfunction "1_1") (pintype "passive"))
      (node (ref "T56") (pin "2") (pinfunction "B_2") (pintype "passive"))
    )
    (net (code "59") (name "/MQ2") (class "Default")
      (node (ref "E40TOP") (pin "13") (pinfunction "1_13") (pintype "passive"))
      (node (ref "T57") (pin "2") (pinfunction "B_2") (pintype "passive"))
    )
    (net (code "60") (name "/MQ3") (class "Default")
      (node (ref "E40BOT") (pin "6") (pinfunction "1_6") (pintype "passive"))
      (node (ref "T58") (pin "2") (pinfunction "B_2") (pintype "passive"))
    )
    (net (code "61") (name "/MQ4") (class "Default")
      (node (ref "E40TOP") (pin "18") (pinfunction "1_18") (pintype "passive"))
      (node (ref "T59") (pin "2") (pinfunction "B_2") (pintype "passive"))
    )
    (net (code "62") (name "/MQ5") (class "Default")
      (node (ref "E40BOT") (pin "15") (pinfunction "1_15") (pintype "passive"))
      (node (ref "T60") (pin "2") (pinfunction "B_2") (pintype "passive"))
    )
    (net (code "63") (name "/MQ6") (class "Default")
      (node (ref "F40TOP") (pin "5") (pinfunction "1_5") (pintype "passive"))
      (node (ref "T61") (pin "2") (pinfunction "B_2") (pintype "passive"))
    )
    (net (code "64") (name "/MQ7") (class "Default")
      (node (ref "F40BOT") (pin "1") (pinfunction "1_1") (pintype "passive"))
      (node (ref "T62") (pin "2") (pinfunction "B_2") (pintype "passive"))
    )
    (net (code "65") (name "/MQ8") (class "Default")
      (node (ref "F40TOP") (pin "13") (pinfunction "1_13") (pintype "passive"))
      (node (ref "T63") (pin "2") (pinfunction "B_2") (pintype "passive"))
    )
    (net (code "66") (name "/MQ9") (class "Default")
      (node (ref "F40BOT") (pin "6") (pinfunction "1_6") (pintype "passive"))
      (node (ref "T64") (pin "2") (pinfunction "B_2") (pintype "passive"))
    )
    (net (code "67") (name "/MQ10") (class "Default")
      (node (ref "F40TOP") (pin "18") (pinfunction "1_18") (pintype "passive"))
      (node (ref "T65") (pin "2") (pinfunction "B_2") (pintype "passive"))
    )
    (net (code "68") (name "/MQ11") (class "Default")
      (node (ref "F40BOT") (pin "15") (pinfunction "1_15") (pintype "passive"))
      (node (ref "T66") (pin "2") (pinfunction "B_2") (pintype "passive"))
    )
    (net (code "69") (name "/OPR") (class "Default")
      (node (ref "D40BOT") (pin "11") (pinfunction "1_11") (pintype "passive"))
      (node (ref "T89") (pin "2") (pinfunction "B_2") (pintype "passive"))
    )
    (net (code "70") (name "/PAUSE") (class "Default")
      (node (ref "D40TOP") (pin "17") (pinfunction "1_17") (pintype "passive"))
      (node (ref "T74") (pin "2") (pinfunction "B_2") (pintype "passive"))
    )
    (net (code "71") (name "/PC0") (class "Default")
      (node (ref "E40TOP") (pin "1") (pinfunction "1_1") (pintype "passive"))
      (node (ref "T7") (pin "2") (pinfunction "B_2") (pintype "passive"))
    )
    (net (code "72") (name "/PC1") (class "Default")
      (node (ref "E40BOT") (pin "5") (pinfunction "1_5") (pintype "passive"))
      (node (ref "T8") (pin "2") (pinfunction "B_2") (pintype "passive"))
    )
    (net (code "73") (name "/PC2") (class "Default")
      (node (ref "E40TOP") (pin "6") (pinfunction "1_6") (pintype "passive"))
      (node (ref "T9") (pin "2") (pinfunction "B_2") (pintype "passive"))
    )
    (net (code "74") (name "/PC3") (class "Default")
      (node (ref "E40BOT") (pin "14") (pinfunction "1_14") (pintype "passive"))
      (node (ref "T10") (pin "2") (pinfunction "B_2") (pintype "passive"))
    )
    (net (code "75") (name "/PC4") (class "Default")
      (node (ref "E40TOP") (pin "14") (pinfunction "1_14") (pintype "passive"))
      (node (ref "T11") (pin "2") (pinfunction "B_2") (pintype "passive"))
    )
    (net (code "76") (name "/PC5") (class "Default")
      (node (ref "E40BOT") (pin "19") (pinfunction "1_19") (pintype "passive"))
      (node (ref "T12") (pin "2") (pinfunction "B_2") (pintype "passive"))
    )
    (net (code "77") (name "/PC6") (class "Default")
      (node (ref "F40TOP") (pin "1") (pinfunction "1_1") (pintype "passive"))
      (node (ref "T13") (pin "2") (pinfunction "B_2") (pintype "passive"))
    )
    (net (code "78") (name "/PC7") (class "Default")
      (node (ref "F40BOT") (pin "5") (pinfunction "1_5") (pintype "passive"))
      (node (ref "T14") (pin "2") (pinfunction "B_2") (pintype "passive"))
    )
    (net (code "79") (name "/PC8") (class "Default")
      (node (ref "F40TOP") (pin "6") (pinfunction "1_6") (pintype "passive"))
      (node (ref "T15") (pin "2") (pinfunction "B_2") (pintype "passive"))
    )
    (net (code "80") (name "/PC9") (class "Default")
      (node (ref "F40BOT") (pin "14") (pinfunction "1_14") (pintype "passive"))
      (node (ref "T16") (pin "2") (pinfunction "B_2") (pintype "passive"))
    )
    (net (code "81") (name "/PC10") (class "Default")
      (node (ref "F40TOP") (pin "14") (pinfunction "1_14") (pintype "passive"))
      (node (ref "T17") (pin "2") (pinfunction "B_2") (pintype "passive"))
    )
    (net (code "82") (name "/PC11") (class "Default")
      (node (ref "F40BOT") (pin "19") (pinfunction "1_19") (pintype "passive"))
      (node (ref "T18") (pin "2") (pinfunction "B_2") (pintype "passive"))
    )
    (net (code "83") (name "/RUN") (class "Default")
      (node (ref "D40TOP") (pin "18") (pinfunction "1_18") (pintype "passive"))
      (node (ref "T75") (pin "2") (pinfunction "B_2") (pintype "passive"))
    )
    (net (code "84") (name "/SC0") (class "Default")
      (node (ref "C40TOP") (pin "5") (pinfunction "1_5") (pintype "passive"))
      (node (ref "T67") (pin "2") (pinfunction "B_2") (pintype "passive"))
    )
    (net (code "85") (name "/SC1") (class "Default")
      (node (ref "C40BOT") (pin "1") (pinfunction "1_1") (pintype "passive"))
      (node (ref "T68") (pin "2") (pinfunction "B_2") (pintype "passive"))
    )
    (net (code "86") (name "/SC2") (class "Default")
      (node (ref "C40TOP") (pin "13") (pinfunction "1_13") (pintype "passive"))
      (node (ref "T69") (pin "2") (pinfunction "B_2") (pintype "passive"))
    )
    (net (code "87") (name "/SC3") (class "Default")
      (node (ref "C40BOT") (pin "6") (pinfunction "1_6") (pintype "passive"))
      (node (ref "T70") (pin "2") (pinfunction "B_2") (pintype "passive"))
    )
    (net (code "88") (name "/SC4") (class "Default")
      (node (ref "C40TOP") (pin "18") (pinfunction "1_18") (pintype "passive"))
      (node (ref "T71") (pin "2") (pinfunction "B_2") (pintype "passive"))
    )
    (net (code "89") (name "/TAD") (class "Default")
      (node (ref "D40BOT") (pin "2") (pinfunction "1_2") (pintype "passive"))
      (node (ref "T83") (pin "2") (pinfunction "B_2") (pintype "passive"))
    )
    (net (code "90") (name "/WC") (class "Default")
      (node (ref "D40BOT") (pin "17") (pinfunction "1_17") (pintype "passive"))
      (node (ref "T79") (pin "2") (pinfunction "B_2") (pintype "passive"))
    )
    (net (code "91") (name "GND") (class "Default")
      (node (ref "GND") (pin "1") (pinfunction "1_1") (pintype "passive"))
      (node (ref "T1") (pin "1") (pinfunction "E_1") (pintype "passive"))
      (node (ref "T10") (pin "1") (pinfunction "E_1") (pintype "passive"))
      (node (ref "T11") (pin "1") (pinfunction "E_1") (pintype "passive"))
      (node (ref "T12") (pin "1") (pinfunction "E_1") (pintype "passive"))
      (node (ref "T13") (pin "1") (pinfunction "E_1") (pintype "passive"))
      (node (ref "T14") (pin "1") (pinfunction "E_1") (pintype "passive"))
      (node (ref "T15") (pin "1") (pinfunction "E_1") (pintype "passive"))
      (node (ref "T16") (pin "1") (pinfunction "E_1") (pintype "passive"))
      (node (ref "T17") (pin "1") (pinfunction "E_1") (pintype "passive"))
      (node (ref "T18") (pin "1") (pinfunction "E_1") (pintype "passive"))
      (node (ref "T19") (pin "1") (pinfunction "E_1") (pintype "passive"))
      (node (ref "T2") (pin "1") (pinfunction "E_1") (pintype "passive"))
      (node (ref "T20") (pin "1") (pinfunction "E_1") (pintype "passive"))
      (node (ref "T21") (pin "1") (pinfunction "E_1") (pintype "passive"))
      (node (ref "T22") (pin "1") (pinfunction "E_1") (pintype "passive"))
      (node (ref "T23") (pin "1") (pinfunction "E_1") (pintype "passive"))
      (node (ref "T24") (pin "1") (pinfunction "E_1") (pintype "passive"))
      (node (ref "T25") (pin "1") (pinfunction "E_1") (pintype "passive"))
      (node (ref "T26") (pin "1") (pinfunction "E_1") (pintype "passive"))
      (node (ref "T27") (pin "1") (pinfunction "E_1") (pintype "passive"))
      (node (ref "T28") (pin "1") (pinfunction "E_1") (pintype "passive"))
      (node (ref "T29") (pin "1") (pinfunction "E_1") (pintype "passive"))
      (node (ref "T3") (pin "1") (pinfunction "E_1") (pintype "passive"))
      (node (ref "T30") (pin "1") (pinfunction "E_1") (pintype "passive"))
      (node (ref "T31") (pin "1") (pinfunction "E_1") (pintype "passive"))
      (node (ref "T32") (pin "1") (pinfunction "E_1") (pintype "passive"))
      (node (ref "T33") (pin "1") (pinfunction "E_1") (pintype "passive"))
      (node (ref "T34") (pin "1") (pinfunction "E_1") (pintype "passive"))
      (node (ref "T35") (pin "1") (pinfunction "E_1") (pintype "passive"))
      (node (ref "T36") (pin "1") (pinfunction "E_1") (pintype "passive"))
      (node (ref "T37") (pin "1") (pinfunction "E_1") (pintype "passive"))
      (node (ref "T38") (pin "1") (pinfunction "E_1") (pintype "passive"))
      (node (ref "T39") (pin "1") (pinfunction "E_1") (pintype "passive"))
      (node (ref "T4") (pin "1") (pinfunction "E_1") (pintype "passive"))
      (node (ref "T40") (pin "1") (pinfunction "E_1") (pintype "passive"))
      (node (ref "T41") (pin "1") (pinfunction "E_1") (pintype "passive"))
      (node (ref "T42") (pin "1") (pinfunction "E_1") (pintype "passive"))
      (node (ref "T43") (pin "1") (pinfunction "E_1") (pintype "passive"))
      (node (ref "T44") (pin "1") (pinfunction "E_1") (pintype "passive"))
      (node (ref "T45") (pin "1") (pinfunction "E_1") (pintype "passive"))
      (node (ref "T46") (pin "1") (pinfunction "E_1") (pintype "passive"))
      (node (ref "T47") (pin "1") (pinfunction "E_1") (pintype "passive"))
      (node (ref "T48") (pin "1") (pinfunction "E_1") (pintype "passive"))
      (node (ref "T49") (pin "1") (pinfunction "E_1") (pintype "passive"))
      (node (ref "T5") (pin "1") (pinfunction "E_1") (pintype "passive"))
      (node (ref "T50") (pin "1") (pinfunction "E_1") (pintype "passive"))
      (node (ref "T51") (pin "1") (pinfunction "E_1") (pintype "passive"))
      (node (ref "T52") (pin "1") (pinfunction "E_1") (pintype "passive"))
      (node (ref "T53") (pin "1") (pinfunction "E_1") (pintype "passive"))
      (node (ref "T54") (pin "1") (pinfunction "E_1") (pintype "passive"))
      (node (ref "T55") (pin "1") (pinfunction "E_1") (pintype "passive"))
      (node (ref "T56") (pin "1") (pinfunction "E_1") (pintype "passive"))
      (node (ref "T57") (pin "1") (pinfunction "E_1") (pintype "passive"))
      (node (ref "T58") (pin "1") (pinfunction "E_1") (pintype "passive"))
      (node (ref "T59") (pin "1") (pinfunction "E_1") (pintype "passive"))
      (node (ref "T6") (pin "1") (pinfunction "E_1") (pintype "passive"))
      (node (ref "T60") (pin "1") (pinfunction "E_1") (pintype "passive"))
      (node (ref "T61") (pin "1") (pinfunction "E_1") (pintype "passive"))
      (node (ref "T62") (pin "1") (pinfunction "E_1") (pintype "passive"))
      (node (ref "T63") (pin "1") (pinfunction "E_1") (pintype "passive"))
      (node (ref "T64") (pin "1") (pinfunction "E_1") (pintype "passive"))
      (node (ref "T65") (pin "1") (pinfunction "E_1") (pintype "passive"))
      (node (ref "T66") (pin "1") (pinfunction "E_1") (pintype "passive"))
      (node (ref "T67") (pin "1") (pinfunction "E_1") (pintype "passive"))
      (node (ref "T68") (pin "1") (pinfunction "E_1") (pintype "passive"))
      (node (ref "T69") (pin "1") (pinfunction "E_1") (pintype "passive"))
      (node (ref "T7") (pin "1") (pinfunction "E_1") (pintype "passive"))
      (node (ref "T70") (pin "1") (pinfunction "E_1") (pintype "passive"))
      (node (ref "T71") (pin "1") (pinfunction "E_1") (pintype "passive"))
      (node (ref "T72") (pin "1") (pinfunction "E_1") (pintype "passive"))
      (node (ref "T73") (pin "1") (pinfunction "E_1") (pintype "passive"))
      (node (ref "T74") (pin "1") (pinfunction "E_1") (pintype "passive"))
      (node (ref "T75") (pin "1") (pinfunction "E_1") (pintype "passive"))
      (node (ref "T76") (pin "1") (pinfunction "E_1") (pintype "passive"))
      (node (ref "T77") (pin "1") (pinfunction "E_1") (pintype "passive"))
      (node (ref "T78") (pin "1") (pinfunction "E_1") (pintype "passive"))
      (node (ref "T79") (pin "1") (pinfunction "E_1") (pintype "passive"))
      (node (ref "T8") (pin "1") (pinfunction "E_1") (pintype "passive"))
      (node (ref "T80") (pin "1") (pinfunction "E_1") (pintype "passive"))
      (node (ref "T81") (pin "1") (pinfunction "E_1") (pintype "passive"))
      (node (ref "T82") (pin "1") (pinfunction "E_1") (pintype "passive"))
      (node (ref "T83") (pin "1") (pinfunction "E_1") (pintype "passive"))
      (node (ref "T84") (pin "1") (pinfunction "E_1") (pintype "passive"))
      (node (ref "T85") (pin "1") (pinfunction "E_1") (pintype "passive"))
      (node (ref "T86") (pin "1") (pinfunction "E_1") (pintype "passive"))
      (node (ref "T87") (pin "1") (pinfunction "E_1") (pintype "passive"))
      (node (ref "T88") (pin "1") (pinfunction "E_1") (pintype "passive"))
      (node (ref "T89") (pin "1") (pinfunction "E_1") (pintype "passive"))
      (node (ref "T9") (pin "1") (pinfunction "E_1") (pintype "passive"))
    )
    (net (code "92") (name "Net-(T1-C)") (class "Default")
      (node (ref "DF0") (pin "B") (pinfunction "B_B") (pintype "passive"))
      (node (ref "T1") (pin "3") (pinfunction "C_3") (pintype "passive"))
    )
    (net (code "93") (name "Net-(T2-C)") (class "Default")
      (node (ref "DF1") (pin "B") (pinfunction "B_B") (pintype "passive"))
      (node (ref "T2") (pin "3") (pinfunction "C_3") (pintype "passive"))
    )
    (net (code "94") (name "Net-(T3-C)") (class "Default")
      (node (ref "DF2") (pin "B") (pinfunction "B_B") (pintype "passive"))
      (node (ref "T3") (pin "3") (pinfunction "C_3") (pintype "passive"))
    )
    (net (code "95") (name "Net-(T4-C)") (class "Default")
      (node (ref "IF0") (pin "B") (pinfunction "B_B") (pintype "passive"))
      (node (ref "T4") (pin "3") (pinfunction "C_3") (pintype "passive"))
    )
    (net (code "96") (name "Net-(T5-C)") (class "Default")
      (node (ref "IF1") (pin "B") (pinfunction "B_B") (pintype "passive"))
      (node (ref "T5") (pin "3") (pinfunction "C_3") (pintype "passive"))
    )
    (net (code "97") (name "Net-(T6-C)") (class "Default")
      (node (ref "IF2") (pin "B") (pinfunction "B_B") (pintype "passive"))
      (node (ref "T6") (pin "3") (pinfunction "C_3") (pintype "passive"))
    )
    (net (code "98") (name "Net-(T7-C)") (class "Default")
      (node (ref "PC0") (pin "B") (pinfunction "B_B") (pintype "passive"))
      (node (ref "T7") (pin "3") (pinfunction "C_3") (pintype "passive"))
    )
    (net (code "99") (name "Net-(T8-C)") (class "Default")
      (node (ref "PC1") (pin "B") (pinfunction "B_B") (pintype "passive"))
      (node (ref "T8") (pin "3") (pinfunction "C_3") (pintype "passive"))
    )
    (net (code "100") (name "Net-(T9-C)") (class "Default")
      (node (ref "PC2") (pin "B") (pinfunction "B_B") (pintype "passive"))
      (node (ref "T9") (pin "3") (pinfunction "C_3") (pintype "passive"))
    )
    (net (code "101") (name "Net-(T10-C)") (class "Default")
      (node (ref "PC3") (pin "B") (pinfunction "B_B") (pintype "passive"))
      (node (ref "T10") (pin "3") (pinfunction "C_3") (pintype "passive"))
    )
    (net (code "102") (name "Net-(T11-C)") (class "Default")
      (node (ref "PC4") (pin "B") (pinfunction "B_B") (pintype "passive"))
      (node (ref "T11") (pin "3") (pinfunction "C_3") (pintype "passive"))
    )
    (net (code "103") (name "Net-(T12-C)") (class "Default")
      (node (ref "PC5") (pin "B") (pinfunction "B_B") (pintype "passive"))
      (node (ref "T12") (pin "3") (pinfunction "C_3") (pintype "passive"))
    )
    (net (code "104") (name "Net-(T13-C)") (class "Default")
      (node (ref "PC6") (pin "B") (pinfunction "B_B") (pintype "passive"))
      (node (ref "T13") (pin "3") (pinfunction "C_3") (pintype "passive"))
    )
    (net (code "105") (name "Net-(T14-C)") (class "Default")
      (node (ref "PC7") (pin "B") (pinfunction "B_B") (pintype "passive"))
      (node (ref "T14") (pin "3") (pinfunction "C_3") (pintype "passive"))
    )
    (net (code "106") (name "Net-(T15-C)") (class "Default")
      (node (ref "PC8") (pin "B") (pinfunction "B_B") (pintype "passive"))
      (node (ref "T15") (pin "3") (pinfunction "C_3") (pintype "passive"))
    )
    (net (code "107") (name "Net-(T16-C)") (class "Default")
      (node (ref "PC9") (pin "B") (pinfunction "B_B") (pintype "passive"))
      (node (ref "T16") (pin "3") (pinfunction "C_3") (pintype "passive"))
    )
    (net (code "108") (name "Net-(T17-C)") (class "Default")
      (node (ref "PC10") (pin "B") (pinfunction "B_B") (pintype "passive"))
      (node (ref "T17") (pin "3") (pinfunction "C_3") (pintype "passive"))
    )
    (net (code "109") (name "Net-(T18-C)") (class "Default")
      (node (ref "PC11") (pin "B") (pinfunction "B_B") (pintype "passive"))
      (node (ref "T18") (pin "3") (pinfunction "C_3") (pintype "passive"))
    )
    (net (code "110") (name "Net-(T19-C)") (class "Default")
      (node (ref "MA0") (pin "B") (pinfunction "B_B") (pintype "passive"))
      (node (ref "T19") (pin "3") (pinfunction "C_3") (pintype "passive"))
    )
    (net (code "111") (name "Net-(T20-C)") (class "Default")
      (node (ref "MA1") (pin "B") (pinfunction "B_B") (pintype "passive"))
      (node (ref "T20") (pin "3") (pinfunction "C_3") (pintype "passive"))
    )
    (net (code "112") (name "Net-(T21-C)") (class "Default")
      (node (ref "MA2") (pin "B") (pinfunction "B_B") (pintype "passive"))
      (node (ref "T21") (pin "3") (pinfunction "C_3") (pintype "passive"))
    )
    (net (code "113") (name "Net-(T22-C)") (class "Default")
      (node (ref "MA3") (pin "B") (pinfunction "B_B") (pintype "passive"))
      (node (ref "T22") (pin "3") (pinfunction "C_3") (pintype "passive"))
    )
    (net (code "114") (name "Net-(T23-C)") (class "Default")
      (node (ref "MA4") (pin "B") (pinfunction "B_B") (pintype "passive"))
      (node (ref "T23") (pin "3") (pinfunction "C_3") (pintype "passive"))
    )
    (net (code "115") (name "Net-(T24-C)") (class "Default")
      (node (ref "MA5") (pin "B") (pinfunction "B_B") (pintype "passive"))
      (node (ref "T24") (pin "3") (pinfunction "C_3") (pintype "passive"))
    )
    (net (code "116") (name "Net-(T25-C)") (class "Default")
      (node (ref "MA6") (pin "B") (pinfunction "B_B") (pintype "passive"))
      (node (ref "T25") (pin "3") (pinfunction "C_3") (pintype "passive"))
    )
    (net (code "117") (name "Net-(T26-C)") (class "Default")
      (node (ref "MA7") (pin "B") (pinfunction "B_B") (pintype "passive"))
      (node (ref "T26") (pin "3") (pinfunction "C_3") (pintype "passive"))
    )
    (net (code "118") (name "Net-(T27-C)") (class "Default")
      (node (ref "MA8") (pin "B") (pinfunction "B_B") (pintype "passive"))
      (node (ref "T27") (pin "3") (pinfunction "C_3") (pintype "passive"))
    )
    (net (code "119") (name "Net-(T28-C)") (class "Default")
      (node (ref "MA9") (pin "B") (pinfunction "B_B") (pintype "passive"))
      (node (ref "T28") (pin "3") (pinfunction "C_3") (pintype "passive"))
    )
    (net (code "120") (name "Net-(T29-C)") (class "Default")
      (node (ref "MA10") (pin "B") (pinfunction "B_B") (pintype "passive"))
      (node (ref "T29") (pin "3") (pinfunction "C_3") (pintype "passive"))
    )
    (net (code "121") (name "Net-(T30-C)") (class "Default")
      (node (ref "MA11") (pin "B") (pinfunction "B_B") (pintype "passive"))
      (node (ref "T30") (pin "3") (pinfunction "C_3") (pintype "passive"))
    )
    (net (code "122") (name "Net-(T31-C)") (class "Default")
      (node (ref "MB0") (pin "B") (pinfunction "B_B") (pintype "passive"))
      (node (ref "T31") (pin "3") (pinfunction "C_3") (pintype "passive"))
    )
    (net (code "123") (name "Net-(T32-C)") (class "Default")
      (node (ref "MB1") (pin "B") (pinfunction "B_B") (pintype "passive"))
      (node (ref "T32") (pin "3") (pinfunction "C_3") (pintype "passive"))
    )
    (net (code "124") (name "Net-(T33-C)") (class "Default")
      (node (ref "MB2") (pin "B") (pinfunction "B_B") (pintype "passive"))
      (node (ref "T33") (pin "3") (pinfunction "C_3") (pintype "passive"))
    )
    (net (code "125") (name "Net-(T34-C)") (class "Default")
      (node (ref "MB3") (pin "B") (pinfunction "B_B") (pintype "passive"))
      (node (ref "T34") (pin "3") (pinfunction "C_3") (pintype "passive"))
    )
    (net (code "126") (name "Net-(T35-C)") (class "Default")
      (node (ref "MB4") (pin "B") (pinfunction "B_B") (pintype "passive"))
      (node (ref "T35") (pin "3") (pinfunction "C_3") (pintype "passive"))
    )
    (net (code "127") (name "Net-(T36-C)") (class "Default")
      (node (ref "MB5") (pin "B") (pinfunction "B_B") (pintype "passive"))
      (node (ref "T36") (pin "3") (pinfunction "C_3") (pintype "passive"))
    )
    (net (code "128") (name "Net-(T37-C)") (class "Default")
      (node (ref "MB6") (pin "B") (pinfunction "B_B") (pintype "passive"))
      (node (ref "T37") (pin "3") (pinfunction "C_3") (pintype "passive"))
    )
    (net (code "129") (name "Net-(T38-C)") (class "Default")
      (node (ref "MB7") (pin "B") (pinfunction "B_B") (pintype "passive"))
      (node (ref "T38") (pin "3") (pinfunction "C_3") (pintype "passive"))
    )
    (net (code "130") (name "Net-(T39-C)") (class "Default")
      (node (ref "MB8") (pin "B") (pinfunction "B_B") (pintype "passive"))
      (node (ref "T39") (pin "3") (pinfunction "C_3") (pintype "passive"))
    )
    (net (code "131") (name "Net-(T40-C)") (class "Default")
      (node (ref "MB9") (pin "B") (pinfunction "B_B") (pintype "passive"))
      (node (ref "T40") (pin "3") (pinfunction "C_3") (pintype "passive"))
    )
    (net (code "132") (name "Net-(T41-C)") (class "Default")
      (node (ref "MB10") (pin "B") (pinfunction "B_B") (pintype "passive"))
      (node (ref "T41") (pin "3") (pinfunction "C_3") (pintype "passive"))
    )
    (net (code "133") (name "Net-(T42-C)") (class "Default")
      (node (ref "MB11") (pin "B") (pinfunction "B_B") (pintype "passive"))
      (node (ref "T42") (pin "3") (pinfunction "C_3") (pintype "passive"))
    )
    (net (code "134") (name "Net-(T43-C)") (class "Default")
      (node (ref "AC0") (pin "B") (pinfunction "B_B") (pintype "passive"))
      (node (ref "T43") (pin "3") (pinfunction "C_3") (pintype "passive"))
    )
    (net (code "135") (name "Net-(T44-C)") (class "Default")
      (node (ref "AC1") (pin "B") (pinfunction "B_B") (pintype "passive"))
      (node (ref "T44") (pin "3") (pinfunction "C_3") (pintype "passive"))
    )
    (net (code "136") (name "Net-(T45-C)") (class "Default")
      (node (ref "AC2") (pin "B") (pinfunction "B_B") (pintype "passive"))
      (node (ref "T45") (pin "3") (pinfunction "C_3") (pintype "passive"))
    )
    (net (code "137") (name "Net-(T46-C)") (class "Default")
      (node (ref "AC3") (pin "B") (pinfunction "B_B") (pintype "passive"))
      (node (ref "T46") (pin "3") (pinfunction "C_3") (pintype "passive"))
    )
    (net (code "138") (name "Net-(T47-C)") (class "Default")
      (node (ref "AC4") (pin "B") (pinfunction "B_B") (pintype "passive"))
      (node (ref "T47") (pin "3") (pinfunction "C_3") (pintype "passive"))
    )
    (net (code "139") (name "Net-(T48-C)") (class "Default")
      (node (ref "AC5") (pin "B") (pinfunction "B_B") (pintype "passive"))
      (node (ref "T48") (pin "3") (pinfunction "C_3") (pintype "passive"))
    )
    (net (code "140") (name "Net-(T49-C)") (class "Default")
      (node (ref "AC6") (pin "B") (pinfunction "B_B") (pintype "passive"))
      (node (ref "T49") (pin "3") (pinfunction "C_3") (pintype "passive"))
    )
    (net (code "141") (name "Net-(T50-C)") (class "Default")
      (node (ref "AC7") (pin "B") (pinfunction "B_B") (pintype "passive"))
      (node (ref "T50") (pin "3") (pinfunction "C_3") (pintype "passive"))
    )
    (net (code "142") (name "Net-(T51-C)") (class "Default")
      (node (ref "AC8") (pin "B") (pinfunction "B_B") (pintype "passive"))
      (node (ref "T51") (pin "3") (pinfunction "C_3") (pintype "passive"))
    )
    (net (code "143") (name "Net-(T52-C)") (class "Default")
      (node (ref "AC9") (pin "B") (pinfunction "B_B") (pintype "passive"))
      (node (ref "T52") (pin "3") (pinfunction "C_3") (pintype "passive"))
    )
    (net (code "144") (name "Net-(T53-C)") (class "Default")
      (node (ref "AC10") (pin "B") (pinfunction "B_B") (pintype "passive"))
      (node (ref "T53") (pin "3") (pinfunction "C_3") (pintype "passive"))
    )
    (net (code "145") (name "Net-(T54-C)") (class "Default")
      (node (ref "AC11") (pin "B") (pinfunction "B_B") (pintype "passive"))
      (node (ref "T54") (pin "3") (pinfunction "C_3") (pintype "passive"))
    )
    (net (code "146") (name "Net-(T55-C)") (class "Default")
      (node (ref "MQ0") (pin "B") (pinfunction "B_B") (pintype "passive"))
      (node (ref "T55") (pin "3") (pinfunction "C_3") (pintype "passive"))
    )
    (net (code "147") (name "Net-(T56-C)") (class "Default")
      (node (ref "MQ1") (pin "B") (pinfunction "B_B") (pintype "passive"))
      (node (ref "T56") (pin "3") (pinfunction "C_3") (pintype "passive"))
    )
    (net (code "148") (name "Net-(T57-C)") (class "Default")
      (node (ref "MQ2") (pin "B") (pinfunction "B_B") (pintype "passive"))
      (node (ref "T57") (pin "3") (pinfunction "C_3") (pintype "passive"))
    )
    (net (code "149") (name "Net-(T58-C)") (class "Default")
      (node (ref "MQ3") (pin "B") (pinfunction "B_B") (pintype "passive"))
      (node (ref "T58") (pin "3") (pinfunction "C_3") (pintype "passive"))
    )
    (net (code "150") (name "Net-(T59-C)") (class "Default")
      (node (ref "MQ4") (pin "B") (pinfunction "B_B") (pintype "passive"))
      (node (ref "T59") (pin "3") (pinfunction "C_3") (pintype "passive"))
    )
    (net (code "151") (name "Net-(T60-C)") (class "Default")
      (node (ref "MQ5") (pin "B") (pinfunction "B_B") (pintype "passive"))
      (node (ref "T60") (pin "3") (pinfunction "C_3") (pintype "passive"))
    )
    (net (code "152") (name "Net-(T61-C)") (class "Default")
      (node (ref "MQ6") (pin "B") (pinfunction "B_B") (pintype "passive"))
      (node (ref "T61") (pin "3") (pinfunction "C_3") (pintype "passive"))
    )
    (net (code "153") (name "Net-(T62-C)") (class "Default")
      (node (ref "MQ7") (pin "B") (pinfunction "B_B") (pintype "passive"))
      (node (ref "T62") (pin "3") (pinfunction "C_3") (pintype "passive"))
    )
    (net (code "154") (name "Net-(T63-C)") (class "Default")
      (node (ref "MQ8") (pin "B") (pinfunction "B_B") (pintype "passive"))
      (node (ref "T63") (pin "3") (pinfunction "C_3") (pintype "passive"))
    )
    (net (code "155") (name "Net-(T64-C)") (class "Default")
      (node (ref "MQ9") (pin "B") (pinfunction "B_B") (pintype "passive"))
      (node (ref "T64") (pin "3") (pinfunction "C_3") (pintype "passive"))
    )
    (net (code "156") (name "Net-(T65-C)") (class "Default")
      (node (ref "MQ10") (pin "B") (pinfunction "B_B") (pintype "passive"))
      (node (ref "T65") (pin "3") (pinfunction "C_3") (pintype "passive"))
    )
    (net (code "157") (name "Net-(T66-C)") (class "Default")
      (node (ref "MQ11") (pin "B") (pinfunction "B_B") (pintype "passive"))
      (node (ref "T66") (pin "3") (pinfunction "C_3") (pintype "passive"))
    )
    (net (code "158") (name "Net-(T67-C)") (class "Default")
      (node (ref "SC0") (pin "B") (pinfunction "B_B") (pintype "passive"))
      (node (ref "T67") (pin "3") (pinfunction "C_3") (pintype "passive"))
    )
    (net (code "159") (name "Net-(T68-C)") (class "Default")
      (node (ref "SC1") (pin "B") (pinfunction "B_B") (pintype "passive"))
      (node (ref "T68") (pin "3") (pinfunction "C_3") (pintype "passive"))
    )
    (net (code "160") (name "Net-(T69-C)") (class "Default")
      (node (ref "SC2") (pin "B") (pinfunction "B_B") (pintype "passive"))
      (node (ref "T69") (pin "3") (pinfunction "C_3") (pintype "passive"))
    )
    (net (code "161") (name "Net-(T70-C)") (class "Default")
      (node (ref "SC3") (pin "B") (pinfunction "B_B") (pintype "passive"))
      (node (ref "T70") (pin "3") (pinfunction "C_3") (pintype "passive"))
    )
    (net (code "162") (name "Net-(T71-C)") (class "Default")
      (node (ref "SC4") (pin "B") (pinfunction "B_B") (pintype "passive"))
      (node (ref "T71") (pin "3") (pinfunction "C_3") (pintype "passive"))
    )
    (net (code "163") (name "Net-(T72-C)") (class "Default")
      (node (ref "LINK") (pin "B") (pinfunction "B_B") (pintype "passive"))
      (node (ref "T72") (pin "3") (pinfunction "C_3") (pintype "passive"))
    )
    (net (code "164") (name "Net-(T73-C)") (class "Default")
      (node (ref "ION") (pin "B") (pinfunction "B_B") (pintype "passive"))
      (node (ref "T73") (pin "3") (pinfunction "C_3") (pintype "passive"))
    )
    (net (code "165") (name "Net-(T74-C)") (class "Default")
      (node (ref "PAUSE") (pin "B") (pinfunction "B_B") (pintype "passive"))
      (node (ref "T74") (pin "3") (pinfunction "C_3") (pintype "passive"))
    )
    (net (code "166") (name "Net-(T75-C)") (class "Default")
      (node (ref "RUN") (pin "B") (pinfunction "B_B") (pintype "passive"))
      (node (ref "T75") (pin "3") (pinfunction "C_3") (pintype "passive"))
    )
    (net (code "167") (name "Net-(T76-C)") (class "Default")
      (node (ref "FETCH") (pin "B") (pinfunction "B_B") (pintype "passive"))
      (node (ref "T76") (pin "3") (pinfunction "C_3") (pintype "passive"))
    )
    (net (code "168") (name "Net-(T77-C)") (class "Default")
      (node (ref "EXECUTE") (pin "B") (pinfunction "B_B") (pintype "passive"))
      (node (ref "T77") (pin "3") (pinfunction "C_3") (pintype "passive"))
    )
    (net (code "169") (name "Net-(T78-C)") (class "Default")
      (node (ref "DEFER") (pin "B") (pinfunction "B_B") (pintype "passive"))
      (node (ref "T78") (pin "3") (pinfunction "C_3") (pintype "passive"))
    )
    (net (code "170") (name "Net-(T79-C)") (class "Default")
      (node (ref "T79") (pin "3") (pinfunction "C_3") (pintype "passive"))
      (node (ref "WORDCOUNT") (pin "B") (pinfunction "B_B") (pintype "passive"))
    )
    (net (code "171") (name "Net-(T80-C)") (class "Default")
      (node (ref "CURRENTADDRESS") (pin "B") (pinfunction "B_B") (pintype "passive"))
      (node (ref "T80") (pin "3") (pinfunction "C_3") (pintype "passive"))
    )
    (net (code "172") (name "Net-(T81-C)") (class "Default")
      (node (ref "BREAK") (pin "B") (pinfunction "B_B") (pintype "passive"))
      (node (ref "T81") (pin "3") (pinfunction "C_3") (pintype "passive"))
    )
    (net (code "173") (name "Net-(T82-C)") (class "Default")
      (node (ref "AND") (pin "B") (pinfunction "B_B") (pintype "passive"))
      (node (ref "T82") (pin "3") (pinfunction "C_3") (pintype "passive"))
    )
    (net (code "174") (name "Net-(T83-C)") (class "Default")
      (node (ref "T83") (pin "3") (pinfunction "C_3") (pintype "passive"))
      (node (ref "TAD") (pin "B") (pinfunction "B_B") (pintype "passive"))
    )
    (net (code "175") (name "Net-(T84-C)") (class "Default")
      (node (ref "ISZ") (pin "B") (pinfunction "B_B") (pintype "passive"))
      (node (ref "T84") (pin "3") (pinfunction "C_3") (pintype "passive"))
    )
    (net (code "176") (name "Net-(T85-C)") (class "Default")
      (node (ref "DCA") (pin "B") (pinfunction "B_B") (pintype "passive"))
      (node (ref "T85") (pin "3") (pinfunction "C_3") (pintype "passive"))
    )
    (net (code "177") (name "Net-(T86-C)") (class "Default")
      (node (ref "JMS") (pin "B") (pinfunction "B_B") (pintype "passive"))
      (node (ref "T86") (pin "3") (pinfunction "C_3") (pintype "passive"))
    )
    (net (code "178") (name "Net-(T87-C)") (class "Default")
      (node (ref "JMP") (pin "B") (pinfunction "B_B") (pintype "passive"))
      (node (ref "T87") (pin "3") (pinfunction "C_3") (pintype "passive"))
    )
    (net (code "179") (name "Net-(T88-C)") (class "Default")
      (node (ref "IOT") (pin "B") (pinfunction "B_B") (pintype "passive"))
      (node (ref "T88") (pin "3") (pinfunction "C_3") (pintype "passive"))
    )
    (net (code "180") (name "Net-(T89-C)") (class "Default")
      (node (ref "OPR") (pin "B") (pinfunction "B_B") (pintype "passive"))
      (node (ref "T89") (pin "3") (pinfunction "C_3") (pintype "passive"))
    )
    (net (code "181") (name "unconnected-(NC1-Pad1)") (class "Default")
      (node (ref "NC1") (pin "1") (pinfunction "1_1") (pintype "passive"))
    )
    (net (code "182") (name "unconnected-(NC2-Pad1)") (class "Default")
      (node (ref "NC2") (pin "1") (pinfunction "1_1") (pintype "passive"))
    )
  )
)
